# shoff_900.net
KiCad netlist of a schematic drawn in EAGLE
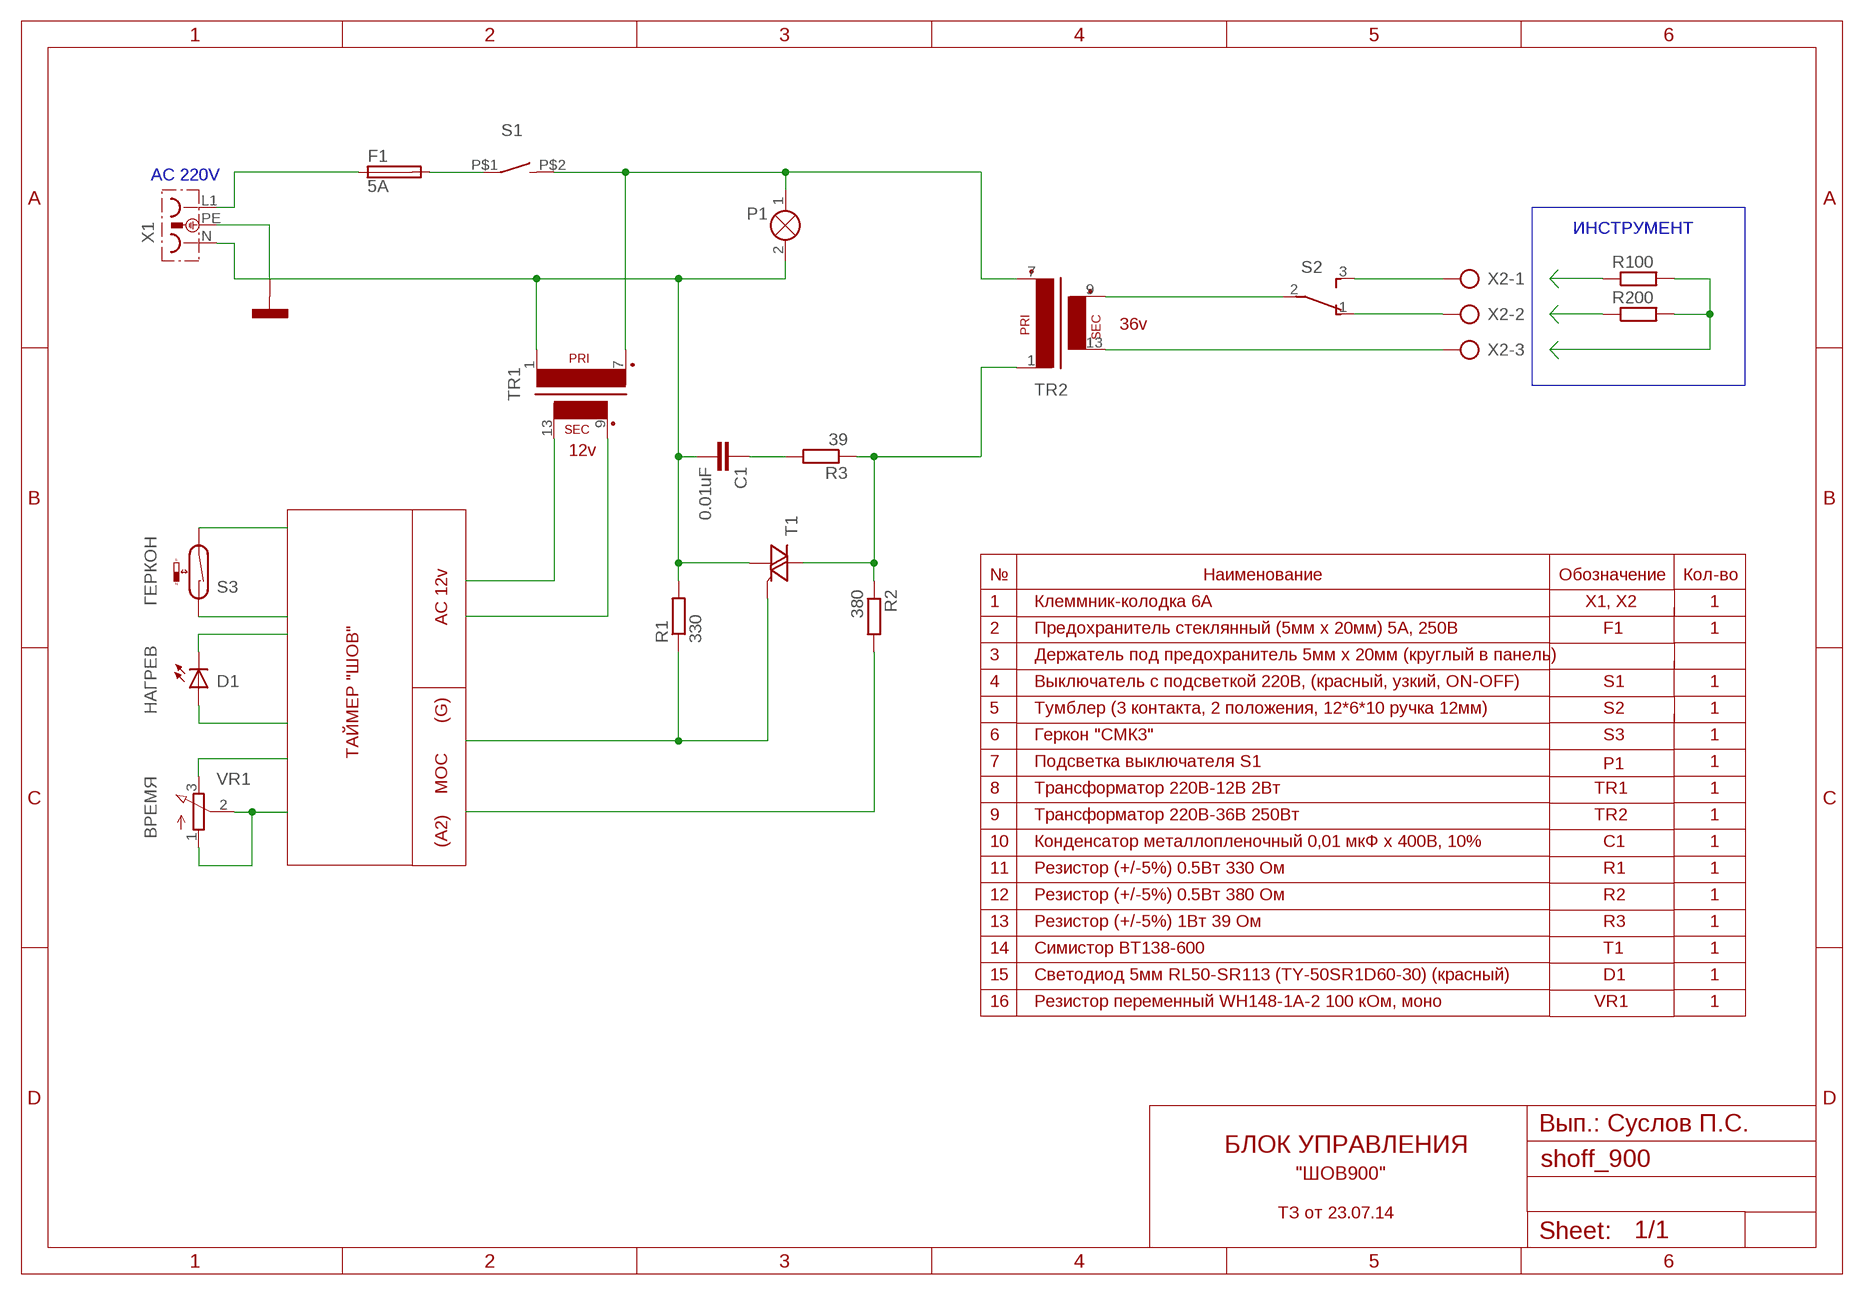
[diagram p0: schematic, sheet 1]

(export (version "E")
  (design (tool "Eeschema 10.0.6"))
  (components
    (comp (ref "C1")
      (value "0.01uF")
      (footprint "eagle-import:C025-030X050")
      (libsource (lib "eagle-import") (part "C-EU025-030X050"))
    )
    (comp (ref "F1")
      (value "5A")
      (footprint "eagle-import:GSH15")
      (fields (field (name "MPN") "64900001039"))
      (libsource (lib "eagle-import") (part "GSH15"))
    )
    (comp (ref "GG")
      (value "MASSE_ALLGEMEIN")
      (footprint "eagle-import:MASSE_ALLGEMEIN")
      (libsource (lib "eagle-import") (part "MASSE_ALLGEMEIN"))
    )
    (comp (ref "P1")
      (value "SIGNALLAMPE")
      (footprint "eagle-import:LAMPE")
      (libsource (lib "eagle-import") (part "SIGNALLAMPE"))
    )
    (comp (ref "R1")
      (value "330")
      (footprint "eagle-import:0207_5V")
      (libsource (lib "eagle-import") (part "R-EU_0207/5V"))
    )
    (comp (ref "R2")
      (value "380")
      (footprint "eagle-import:0207_5V")
      (libsource (lib "eagle-import") (part "R-EU_0207/5V"))
    )
    (comp (ref "R3")
      (value "39")
      (footprint "eagle-import:0207_5V")
      (libsource (lib "eagle-import") (part "R-EU_0207/5V"))
    )
    (comp (ref "R100")
      (value "R-EU_R0201")
      (footprint "eagle-import:R0201")
      (libsource (lib "eagle-import") (part "R-EU_R0201"))
    )
    (comp (ref "R200")
      (value "R-EU_R0201")
      (footprint "eagle-import:R0201")
      (libsource (lib "eagle-import") (part "R-EU_R0201"))
    )
    (comp (ref "S1")
      (value "SCHLIESSER_ARBEITSKONTAKT")
      (footprint "eagle-import:1")
      (libsource (lib "eagle-import") (part "SCHLIESSER_ARBEITSKONTAKT"))
    )
    (comp (ref "S2")
      (value "TL36WO")
      (footprint "eagle-import:TL3XWO")
      (libsource (lib "eagle-import") (part "TL36WO"))
    )
    (comp (ref "S3")
      (value "ГЕРКОН")
      (footprint "eagle-import:CT10-G1")
      (fields (field (name "MF") "COTO TECHNOLOGY") (field (name "MPN") "CT10-1530-G1"))
      (libsource (lib "eagle-import") (part "REED-SWITCH-CT10-1530-G1"))
    )
    (comp (ref "T1")
      (value "BTA26-V")
      (footprint "eagle-import:TOP3S-1")
      (libsource (lib "eagle-import") (part "BTA26-V"))
    )
    (comp (ref "TR1")
      (value "BV054-5381.0K")
      (footprint "eagle-import:EI54-18,8_16VA")
      (libsource (lib "eagle-import") (part "BV054-5381.0K"))
    )
    (comp (ref "TR2")
      (value "BV054-5381.0K")
      (footprint "eagle-import:EI54-18,8_16VA")
      (libsource (lib "eagle-import") (part "BV054-5381.0K"))
    )
    (comp (ref "X1")
      (value "STECKDOSE")
      (footprint "eagle-import:STECKDOSE")
      (libsource (lib "eagle-import") (part "STECKDOSE"))
    )
    (comp (ref "X2")
      (value "AK500/3")
      (footprint "eagle-import:AK500_3")
      (libsource (lib "eagle-import") (part "AK500/3"))
    )
    (comp (ref "ВРЕМЯ")
      (value "3RP/1610N")
      (footprint "eagle-import:3RP_1610N")
      (libsource (lib "eagle-import") (part "3RP/1610N"))
    )
    (comp (ref "ГОТОВ")
      (value "НАГРЕВ")
      (footprint "eagle-import:LED5MM")
      (libsource (lib "eagle-import") (part "LED5MM"))
    )
  )
  (nets
    (net (code "1") (name "Net-(C1-Pad1)") (class "Default")
      (node (ref "C1") (pin "1") (pinfunction "1_1") (pintype "passive"))
      (node (ref "R3") (pin "2") (pinfunction "2_2") (pintype "passive"))
    )
    (net (code "2") (name "Net-(F1-Pad1)") (class "Default")
      (node (ref "F1") (pin "1") (pinfunction "1_1") (pintype "passive"))
      (node (ref "X1") (pin "L1") (pinfunction "L1_L1") (pintype "passive"))
    )
    (net (code "3") (name "Net-(GG-0V)") (class "Default")
      (node (ref "GG") (pin "1") (pinfunction "0V_1") (pintype "passive"))
      (node (ref "X1") (pin "PE") (pinfunction "PE_PE") (pintype "passive"))
    )
    (net (code "4") (name "Net-(P1-X1)") (class "Default")
      (node (ref "P1") (pin "1") (pinfunction "X1_1") (pintype "passive"))
      (node (ref "S1") (pin "P$2") (pinfunction "3_P$2") (pintype "passive"))
      (node (ref "TR1") (pin "7") (pinfunction "P2_7") (pintype "passive"))
      (node (ref "TR2") (pin "7") (pinfunction "P2_7") (pintype "passive"))
    )
    (net (code "5") (name "Net-(P1-X2)") (class "Default")
      (node (ref "C1") (pin "2") (pinfunction "2_2") (pintype "passive"))
      (node (ref "P1") (pin "2") (pinfunction "X2_2") (pintype "passive"))
      (node (ref "R1") (pin "2") (pinfunction "2_2") (pintype "passive"))
      (node (ref "T1") (pin "A1") (pinfunction "A1_A1") (pintype "passive"))
      (node (ref "TR1") (pin "1") (pinfunction "P1_1") (pintype "passive"))
      (node (ref "X1") (pin "N") (pinfunction "N_N") (pintype "passive"))
    )
    (net (code "6") (name "Net-(R1-Pad1)") (class "Default")
      (node (ref "R1") (pin "1") (pinfunction "1_1") (pintype "passive"))
      (node (ref "T1") (pin "G") (pinfunction "G_G") (pintype "passive"))
    )
    (net (code "7") (name "Net-(R100-Pad2)") (class "Default")
      (node (ref "R100") (pin "2") (pinfunction "2_2") (pintype "passive"))
      (node (ref "R200") (pin "2") (pinfunction "2_2") (pintype "passive"))
    )
    (net (code "8") (name "Net-(S1-4)") (class "Default")
      (node (ref "F1") (pin "2") (pinfunction "2_2") (pintype "passive"))
      (node (ref "S1") (pin "P$1") (pinfunction "4_P$1") (pintype "passive"))
    )
    (net (code "9") (name "Net-(S2-O)") (class "Default")
      (node (ref "S2") (pin "1") (pinfunction "O_1") (pintype "passive"))
      (node (ref "X2") (pin "2") (pinfunction "KL_2") (pintype "passive"))
    )
    (net (code "10") (name "Net-(S2-P)") (class "Default")
      (node (ref "S2") (pin "2") (pinfunction "P_2") (pintype "passive"))
      (node (ref "TR2") (pin "9") (pinfunction "S3_9") (pintype "passive"))
    )
    (net (code "11") (name "Net-(S2-S)") (class "Default")
      (node (ref "S2") (pin "3") (pinfunction "S_3") (pintype "passive"))
      (node (ref "X2") (pin "1") (pinfunction "KL_1") (pintype "passive"))
    )
    (net (code "12") (name "Net-(TR2-P1)") (class "Default")
      (node (ref "R2") (pin "1") (pinfunction "1_1") (pintype "passive"))
      (node (ref "R3") (pin "1") (pinfunction "1_1") (pintype "passive"))
      (node (ref "T1") (pin "A2") (pinfunction "A2_A2") (pintype "passive"))
      (node (ref "TR2") (pin "1") (pinfunction "P1_1") (pintype "passive"))
    )
    (net (code "13") (name "Net-(TR2-S4)") (class "Default")
      (node (ref "TR2") (pin "13") (pinfunction "S4_13") (pintype "passive"))
      (node (ref "X2") (pin "3") (pinfunction "KL_3") (pintype "passive"))
    )
    (net (code "14") (name "Net-(ВРЕМЯ-A)") (class "Default")
      (node (ref "ВРЕМЯ") (pin "1") (pinfunction "A_1") (pintype "passive"))
      (node (ref "ВРЕМЯ") (pin "2") (pinfunction "S_2") (pintype "passive"))
    )
    (net (code "15") (name "unconnected-(R2-Pad2)") (class "Default")
      (node (ref "R2") (pin "2") (pinfunction "2_2") (pintype "passive"))
    )
    (net (code "16") (name "unconnected-(R100-Pad1)") (class "Default")
      (node (ref "R100") (pin "1") (pinfunction "1_1") (pintype "passive"))
    )
    (net (code "17") (name "unconnected-(R200-Pad1)") (class "Default")
      (node (ref "R200") (pin "1") (pinfunction "1_1") (pintype "passive"))
    )
    (net (code "18") (name "unconnected-(S3-Pad1)") (class "Default")
      (node (ref "S3") (pin "1") (pinfunction "1_1") (pintype "passive"))
    )
    (net (code "19") (name "unconnected-(S3-Pad2)") (class "Default")
      (node (ref "S3") (pin "2") (pinfunction "2_2") (pintype "passive"))
    )
    (net (code "20") (name "unconnected-(TR1-S3-Pad9)") (class "Default")
      (node (ref "TR1") (pin "9") (pinfunction "S3_9") (pintype "passive"))
    )
    (net (code "21") (name "unconnected-(TR1-S4-Pad13)") (class "Default")
      (node (ref "TR1") (pin "13") (pinfunction "S4_13") (pintype "passive"))
    )
    (net (code "22") (name "unconnected-(ВРЕМЯ-E-Pad3)") (class "Default")
      (node (ref "ВРЕМЯ") (pin "3") (pinfunction "E_3") (pintype "passive"))
    )
    (net (code "23") (name "unconnected-(ГОТОВ-C-PadK)") (class "Default")
      (node (ref "ГОТОВ") (pin "K") (pinfunction "C_K") (pintype "passive"))
    )
    (net (code "24") (name "unconnected-(ГОТОВ-PadA)") (class "Default")
      (node (ref "ГОТОВ") (pin "A") (pinfunction "A_A") (pintype "passive"))
    )
  )
)
